# Sheet1.net
KiCad netlist of a schematic drawn in Altium Designer
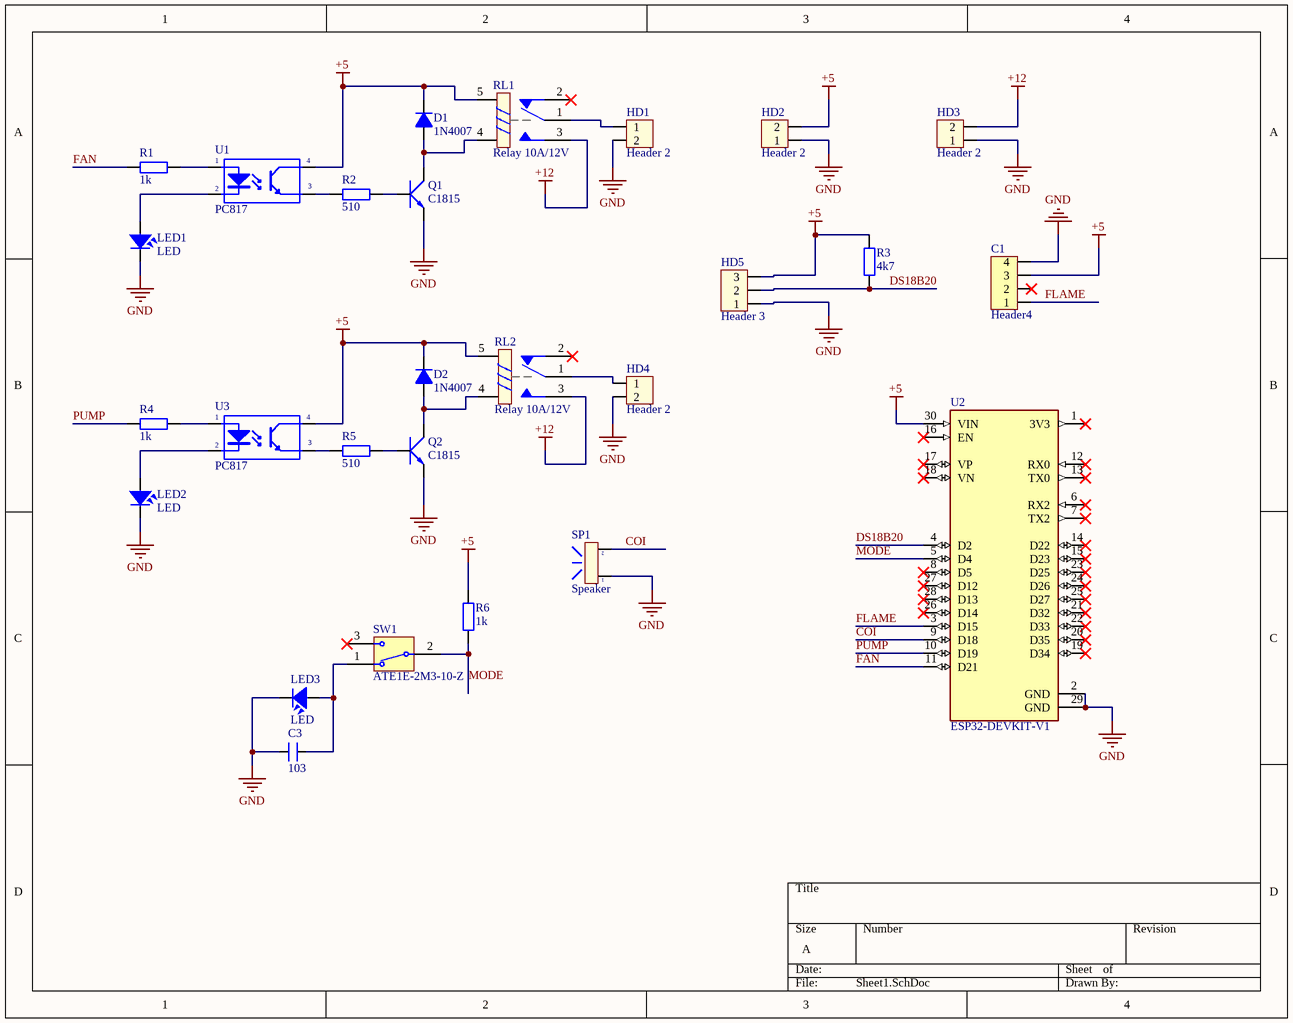
[diagram p0: Sheet1.SchDoc]

(export (version "E")
  (design (tool "Eeschema 10.0.6"))
  (components
    (comp (ref "C1")
      (value "Header4")
      (footprint "Header4")
      (description "Header IDC, 4 x 1 Pin Vertical 2.54mm Pitch (Non-Boxed, Male)")
      (fields
        (field (name "MANUFACTURER") "Würth Elektronik eiSos GmbH")
        (field (name "PARTNO") "613002143121")
        (field (name "CREATED BY") "Karrer Zheng")
      )
      (libsource (lib "myLib_v1") (part "Header4"))
    )
    (comp (ref "C3")
      (value "103")
      (footprint "CN1.5")
      (description "Cap np 682pF => 104pF")
      (libsource (lib "syhaunguyen") (part "CN1.5"))
    )
    (comp (ref "D1")
      (value "1N4007")
      (footprint "D1A")
      (description "Diode 1A")
      (libsource (lib "syhaunguyen") (part "D1A"))
    )
    (comp (ref "D2")
      (value "1N4007")
      (footprint "D1A")
      (description "Diode 1A")
      (libsource (lib "syhaunguyen") (part "D1A"))
    )
    (comp (ref "HD1")
      (value "Header 2")
      (footprint "HED2")
      (description "Header 2 (Green)")
      (libsource (lib "") (part "Hed2_1"))
    )
    (comp (ref "HD2")
      (value "Header 2")
      (footprint "HED2")
      (description "Header 2 (Green)")
      (libsource (lib "syhaunguyen") (part "Hed2"))
    )
    (comp (ref "HD3")
      (value "Header 2")
      (footprint "HED2")
      (description "Header 2 (Green)")
      (libsource (lib "syhaunguyen") (part "Hed2"))
    )
    (comp (ref "HD4")
      (value "Header 2")
      (footprint "HED2")
      (description "Header 2 (Green)")
      (libsource (lib "") (part "Hed2_1"))
    )
    (comp (ref "HD5")
      (value "Header 3")
      (footprint "HED3")
      (description "Header 3 (Green)")
      (libsource (lib "syhaunguyen") (part "Hed3"))
    )
    (comp (ref "LED1")
      (value "LED")
      (footprint "LED-3")
      (description "LED Single colour Green and Red")
      (libsource (lib "syhaunguyen") (part "LED"))
    )
    (comp (ref "LED2")
      (value "LED")
      (footprint "LED-3")
      (description "LED Single colour Green and Red")
      (libsource (lib "syhaunguyen") (part "LED"))
    )
    (comp (ref "LED3")
      (value "LED")
      (footprint "LED-3")
      (description "LED Single colour Green and Red")
      (libsource (lib "syhaunguyen") (part "LED"))
    )
    (comp (ref "Q1")
      (value "C1815")
      (footprint "QTO-92")
      (description "NPN 600mW, ECB")
      (libsource (lib "syhaunguyen") (part "C1815"))
    )
    (comp (ref "Q2")
      (value "C1815")
      (footprint "QTO-92")
      (description "NPN 600mW, ECB")
      (libsource (lib "syhaunguyen") (part "C1815"))
    )
    (comp (ref "R1")
      (value "1k")
      (footprint "R1/4W")
      (description "Resistor 1/4W")
      (libsource (lib "syhaunguyen") (part "R1/4W"))
    )
    (comp (ref "R2")
      (value "510")
      (footprint "R1/4W")
      (description "Resistor 1/4W")
      (libsource (lib "syhaunguyen") (part "R1/4W"))
    )
    (comp (ref "R3")
      (value "4k7")
      (footprint "R1/4W")
      (description "Resistor 1/4W")
      (libsource (lib "syhaunguyen") (part "R1/4W"))
    )
    (comp (ref "R4")
      (value "1k")
      (footprint "R1/4W")
      (description "Resistor 1/4W")
      (libsource (lib "syhaunguyen") (part "R1/4W"))
    )
    (comp (ref "R5")
      (value "510")
      (footprint "R1/4W")
      (description "Resistor 1/4W")
      (libsource (lib "syhaunguyen") (part "R1/4W"))
    )
    (comp (ref "R6")
      (value "1k")
      (footprint "R1/4W")
      (description "Resistor 1/4W")
      (libsource (lib "syhaunguyen") (part "R1/4W"))
    )
    (comp (ref "RL1")
      (value "Relay 10A/12V")
      (footprint "RL_SPDT_10A")
      (description "Relay SPDT,10A - 12VDC 5 Pin")
      (libsource (lib "Cty1") (part "Relay 1"))
    )
    (comp (ref "RL2")
      (value "Relay 10A/12V")
      (footprint "RL_SPDT_10A")
      (description "Relay SPDT,10A - 12VDC 5 Pin")
      (libsource (lib "Cty1") (part "Relay 1"))
    )
    (comp (ref "SP1")
      (value "Speaker")
      (footprint "SPK")
      (description "Speaker Chip")
      (libsource (lib "Thuvien3D") (part "SPK"))
    )
    (comp (ref "SW1")
      (value "ATE1E-2M3-10-Z")
      (footprint "SW_TOGGLE_ATE1E-2M3-10-Z")
      (description "SWITCH TOGGLE SPDT 50MA 48V")
      (fields (field (name "MANUFACTURER") "Copal Electronics Inc."))
      (libsource (lib "KhanhBK_SCH_Lib_6") (part "SW_TOGGLE_ATE1E-2M3-10-Z"))
    )
    (comp (ref "U1")
      (value "PC817")
      (footprint "DIP4/W0.3")
      (description "Single Opto")
      (libsource (lib "syhaunguyen") (part "PC817"))
    )
    (comp (ref "U2")
      (value "ESP32-DEVKIT-V1")
      (footprint "MODULE_ESP32_DEVKIT_V1")
      (fields (field (name "MF") "Do it"))
      (libsource (lib "ESP32-DEVKIT-V1") (part "ESP32-DEVKIT-V1"))
    )
    (comp (ref "U3")
      (value "PC817")
      (footprint "DIP4/W0.3")
      (description "Single Opto")
      (libsource (lib "syhaunguyen") (part "PC817"))
    )
  )
  (nets
    (net (code "1") (name "+5") (class "Default")
      (node (ref "C1") (pin "3") (pinfunction "3_3") (pintype "passive"))
      (node (ref "D1") (pin "2") (pinfunction "K_2") (pintype "passive"))
      (node (ref "D2") (pin "2") (pinfunction "K_2") (pintype "passive"))
      (node (ref "HD2") (pin "2") (pinfunction "2_2") (pintype "passive"))
      (node (ref "HD5") (pin "3") (pinfunction "3_3") (pintype "passive"))
      (node (ref "R3") (pin "2") (pinfunction "2_2") (pintype "passive"))
      (node (ref "R6") (pin "2") (pinfunction "2_2") (pintype "passive"))
      (node (ref "RL1") (pin "5") (pinfunction "5_5") (pintype "passive"))
      (node (ref "RL2") (pin "5") (pinfunction "5_5") (pintype "passive"))
      (node (ref "U1") (pin "4") (pinfunction "C_4") (pintype "passive"))
      (node (ref "U2") (pin "30") (pinfunction "VIN_30") (pintype "input"))
      (node (ref "U3") (pin "4") (pinfunction "C_4") (pintype "passive"))
    )
    (net (code "2") (name "+12") (class "Default")
      (node (ref "HD3") (pin "2") (pinfunction "2_2") (pintype "passive"))
      (node (ref "RL1") (pin "3") (pinfunction "3_3") (pintype "passive"))
      (node (ref "RL2") (pin "3") (pinfunction "3_3") (pintype "passive"))
    )
    (net (code "3") (name "/COI") (class "Default")
      (node (ref "SP1") (pin "2") (pinfunction "2_2") (pintype "passive"))
      (node (ref "U2") (pin "9") (pinfunction "D18_9") (pintype "bidirectional"))
    )
    (net (code "4") (name "/DS18B20") (class "Default")
      (node (ref "HD5") (pin "2") (pinfunction "2_2") (pintype "passive"))
      (node (ref "R3") (pin "1") (pinfunction "1_1") (pintype "passive"))
      (node (ref "U2") (pin "4") (pinfunction "D2_4") (pintype "bidirectional"))
    )
    (net (code "5") (name "/FAN") (class "Default")
      (node (ref "R1") (pin "1") (pinfunction "1_1") (pintype "passive"))
      (node (ref "U2") (pin "11") (pinfunction "D21_11") (pintype "bidirectional"))
    )
    (net (code "6") (name "/FLAME") (class "Default")
      (node (ref "C1") (pin "1") (pinfunction "1_1") (pintype "passive"))
      (node (ref "U2") (pin "3") (pinfunction "D15_3") (pintype "bidirectional"))
    )
    (net (code "7") (name "/MODE") (class "Default")
      (node (ref "R6") (pin "1") (pinfunction "1_1") (pintype "passive"))
      (node (ref "SW1") (pin "2") (pinfunction "COM_2") (pintype "passive"))
      (node (ref "U2") (pin "5") (pinfunction "D4_5") (pintype "bidirectional"))
    )
    (net (code "8") (name "/PUMP") (class "Default")
      (node (ref "R4") (pin "1") (pinfunction "1_1") (pintype "passive"))
      (node (ref "U2") (pin "10") (pinfunction "D19_10") (pintype "bidirectional"))
    )
    (net (code "9") (name "GND") (class "Default")
      (node (ref "C1") (pin "4") (pinfunction "4_4") (pintype "passive"))
      (node (ref "C3") (pin "1") (pinfunction "1_1") (pintype "passive"))
      (node (ref "HD1") (pin "2") (pinfunction "2_2") (pintype "passive"))
      (node (ref "HD2") (pin "1") (pinfunction "1_1") (pintype "passive"))
      (node (ref "HD3") (pin "1") (pinfunction "1_1") (pintype "passive"))
      (node (ref "HD4") (pin "2") (pinfunction "2_2") (pintype "passive"))
      (node (ref "HD5") (pin "1") (pinfunction "1_1") (pintype "passive"))
      (node (ref "LED1") (pin "2") (pinfunction "2_2") (pintype "passive"))
      (node (ref "LED2") (pin "2") (pinfunction "2_2") (pintype "passive"))
      (node (ref "LED3") (pin "2") (pinfunction "2_2") (pintype "passive"))
      (node (ref "Q1") (pin "1") (pinfunction "E_1") (pintype "passive"))
      (node (ref "Q2") (pin "1") (pinfunction "E_1") (pintype "passive"))
      (node (ref "SP1") (pin "1") (pinfunction "1_1") (pintype "passive"))
      (node (ref "U2") (pin "2") (pinfunction "GND_2") (pintype "power_in"))
      (node (ref "U2") (pin "29") (pinfunction "GND_29") (pintype "power_in"))
    )
    (net (code "10") (name "Net-(D1-A)") (class "Default")
      (node (ref "D1") (pin "1") (pinfunction "A_1") (pintype "passive"))
      (node (ref "Q1") (pin "2") (pinfunction "C_2") (pintype "passive"))
      (node (ref "RL1") (pin "4") (pinfunction "4_4") (pintype "passive"))
    )
    (net (code "11") (name "Net-(D2-A)") (class "Default")
      (node (ref "D2") (pin "1") (pinfunction "A_1") (pintype "passive"))
      (node (ref "Q2") (pin "2") (pinfunction "C_2") (pintype "passive"))
      (node (ref "RL2") (pin "4") (pinfunction "4_4") (pintype "passive"))
    )
    (net (code "12") (name "Net-(HD1-Pad1)") (class "Default")
      (node (ref "HD1") (pin "1") (pinfunction "1_1") (pintype "passive"))
      (node (ref "RL1") (pin "1") (pinfunction "1_1") (pintype "passive"))
    )
    (net (code "13") (name "Net-(HD4-Pad1)") (class "Default")
      (node (ref "HD4") (pin "1") (pinfunction "1_1") (pintype "passive"))
      (node (ref "RL2") (pin "1") (pinfunction "1_1") (pintype "passive"))
    )
    (net (code "14") (name "Net-(Q1-B)") (class "Default")
      (node (ref "Q1") (pin "3") (pinfunction "B_3") (pintype "passive"))
      (node (ref "R2") (pin "2") (pinfunction "2_2") (pintype "passive"))
    )
    (net (code "15") (name "Net-(Q2-B)") (class "Default")
      (node (ref "Q2") (pin "3") (pinfunction "B_3") (pintype "passive"))
      (node (ref "R5") (pin "2") (pinfunction "2_2") (pintype "passive"))
    )
    (net (code "16") (name "Net-(SW1-NC)") (class "Default")
      (node (ref "C3") (pin "2") (pinfunction "2_2") (pintype "passive"))
      (node (ref "LED3") (pin "1") (pinfunction "1_1") (pintype "passive"))
      (node (ref "SW1") (pin "1") (pinfunction "NC_1") (pintype "passive"))
    )
    (net (code "17") (name "Net-(U1-A)") (class "Default")
      (node (ref "R1") (pin "2") (pinfunction "2_2") (pintype "passive"))
      (node (ref "U1") (pin "1") (pinfunction "A_1") (pintype "passive"))
    )
    (net (code "18") (name "Net-(U1-E)") (class "Default")
      (node (ref "R2") (pin "1") (pinfunction "1_1") (pintype "passive"))
      (node (ref "U1") (pin "3") (pinfunction "E_3") (pintype "passive"))
    )
    (net (code "19") (name "Net-(U1-K)") (class "Default")
      (node (ref "LED1") (pin "1") (pinfunction "1_1") (pintype "passive"))
      (node (ref "U1") (pin "2") (pinfunction "K_2") (pintype "passive"))
    )
    (net (code "20") (name "Net-(U3-A)") (class "Default")
      (node (ref "R4") (pin "2") (pinfunction "2_2") (pintype "passive"))
      (node (ref "U3") (pin "1") (pinfunction "A_1") (pintype "passive"))
    )
    (net (code "21") (name "Net-(U3-E)") (class "Default")
      (node (ref "R5") (pin "1") (pinfunction "1_1") (pintype "passive"))
      (node (ref "U3") (pin "3") (pinfunction "E_3") (pintype "passive"))
    )
    (net (code "22") (name "Net-(U3-K)") (class "Default")
      (node (ref "LED2") (pin "1") (pinfunction "1_1") (pintype "passive"))
      (node (ref "U3") (pin "2") (pinfunction "K_2") (pintype "passive"))
    )
    (net (code "23") (name "unconnected-(C1-Pad2)") (class "Default")
      (node (ref "C1") (pin "2") (pinfunction "2_2") (pintype "passive+no_connect"))
    )
    (net (code "24") (name "unconnected-(RL1-Pad2)") (class "Default")
      (node (ref "RL1") (pin "2") (pinfunction "2_2") (pintype "passive+no_connect"))
    )
    (net (code "25") (name "unconnected-(RL2-Pad2)") (class "Default")
      (node (ref "RL2") (pin "2") (pinfunction "2_2") (pintype "passive+no_connect"))
    )
    (net (code "26") (name "unconnected-(SW1-NO-Pad3)") (class "Default")
      (node (ref "SW1") (pin "3") (pinfunction "NO_3") (pintype "passive+no_connect"))
    )
    (net (code "27") (name "unconnected-(U2-3V3-Pad1)") (class "Default")
      (node (ref "U2") (pin "1") (pinfunction "3V3_1") (pintype "output+no_connect"))
    )
    (net (code "28") (name "unconnected-(U2-D5-Pad8)") (class "Default")
      (node (ref "U2") (pin "8") (pinfunction "D5_8") (pintype "bidirectional+no_connect"))
    )
    (net (code "29") (name "unconnected-(U2-D12-Pad27)") (class "Default")
      (node (ref "U2") (pin "27") (pinfunction "D12_27") (pintype "bidirectional+no_connect"))
    )
    (net (code "30") (name "unconnected-(U2-D13-Pad28)") (class "Default")
      (node (ref "U2") (pin "28") (pinfunction "D13_28") (pintype "bidirectional+no_connect"))
    )
    (net (code "31") (name "unconnected-(U2-D14-Pad26)") (class "Default")
      (node (ref "U2") (pin "26") (pinfunction "D14_26") (pintype "bidirectional+no_connect"))
    )
    (net (code "32") (name "unconnected-(U2-D22-Pad14)") (class "Default")
      (node (ref "U2") (pin "14") (pinfunction "D22_14") (pintype "bidirectional+no_connect"))
    )
    (net (code "33") (name "unconnected-(U2-D23-Pad15)") (class "Default")
      (node (ref "U2") (pin "15") (pinfunction "D23_15") (pintype "bidirectional+no_connect"))
    )
    (net (code "34") (name "unconnected-(U2-D25-Pad23)") (class "Default")
      (node (ref "U2") (pin "23") (pinfunction "D25_23") (pintype "bidirectional+no_connect"))
    )
    (net (code "35") (name "unconnected-(U2-D26-Pad24)") (class "Default")
      (node (ref "U2") (pin "24") (pinfunction "D26_24") (pintype "bidirectional+no_connect"))
    )
    (net (code "36") (name "unconnected-(U2-D27-Pad25)") (class "Default")
      (node (ref "U2") (pin "25") (pinfunction "D27_25") (pintype "bidirectional+no_connect"))
    )
    (net (code "37") (name "unconnected-(U2-D32-Pad21)") (class "Default")
      (node (ref "U2") (pin "21") (pinfunction "D32_21") (pintype "bidirectional+no_connect"))
    )
    (net (code "38") (name "unconnected-(U2-D33-Pad22)") (class "Default")
      (node (ref "U2") (pin "22") (pinfunction "D33_22") (pintype "bidirectional+no_connect"))
    )
    (net (code "39") (name "unconnected-(U2-D34-Pad19)") (class "Default")
      (node (ref "U2") (pin "19") (pinfunction "D34_19") (pintype "bidirectional+no_connect"))
    )
    (net (code "40") (name "unconnected-(U2-D35-Pad20)") (class "Default")
      (node (ref "U2") (pin "20") (pinfunction "D35_20") (pintype "bidirectional+no_connect"))
    )
    (net (code "41") (name "unconnected-(U2-EN-Pad16)") (class "Default")
      (node (ref "U2") (pin "16") (pinfunction "EN_16") (pintype "input+no_connect"))
    )
    (net (code "42") (name "unconnected-(U2-RX0-Pad12)") (class "Default")
      (node (ref "U2") (pin "12") (pinfunction "RX0_12") (pintype "input+no_connect"))
    )
    (net (code "43") (name "unconnected-(U2-RX2-Pad6)") (class "Default")
      (node (ref "U2") (pin "6") (pinfunction "RX2_6") (pintype "input+no_connect"))
    )
    (net (code "44") (name "unconnected-(U2-TX0-Pad13)") (class "Default")
      (node (ref "U2") (pin "13") (pinfunction "TX0_13") (pintype "output+no_connect"))
    )
    (net (code "45") (name "unconnected-(U2-TX2-Pad7)") (class "Default")
      (node (ref "U2") (pin "7") (pinfunction "TX2_7") (pintype "output+no_connect"))
    )
    (net (code "46") (name "unconnected-(U2-VN-Pad18)") (class "Default")
      (node (ref "U2") (pin "18") (pinfunction "VN_18") (pintype "bidirectional+no_connect"))
    )
    (net (code "47") (name "unconnected-(U2-VP-Pad17)") (class "Default")
      (node (ref "U2") (pin "17") (pinfunction "VP_17") (pintype "bidirectional+no_connect"))
    )
  )
)
